# PSoC_Motor_Driver_Design_3.net
KiCad netlist of a schematic drawn in EAGLE
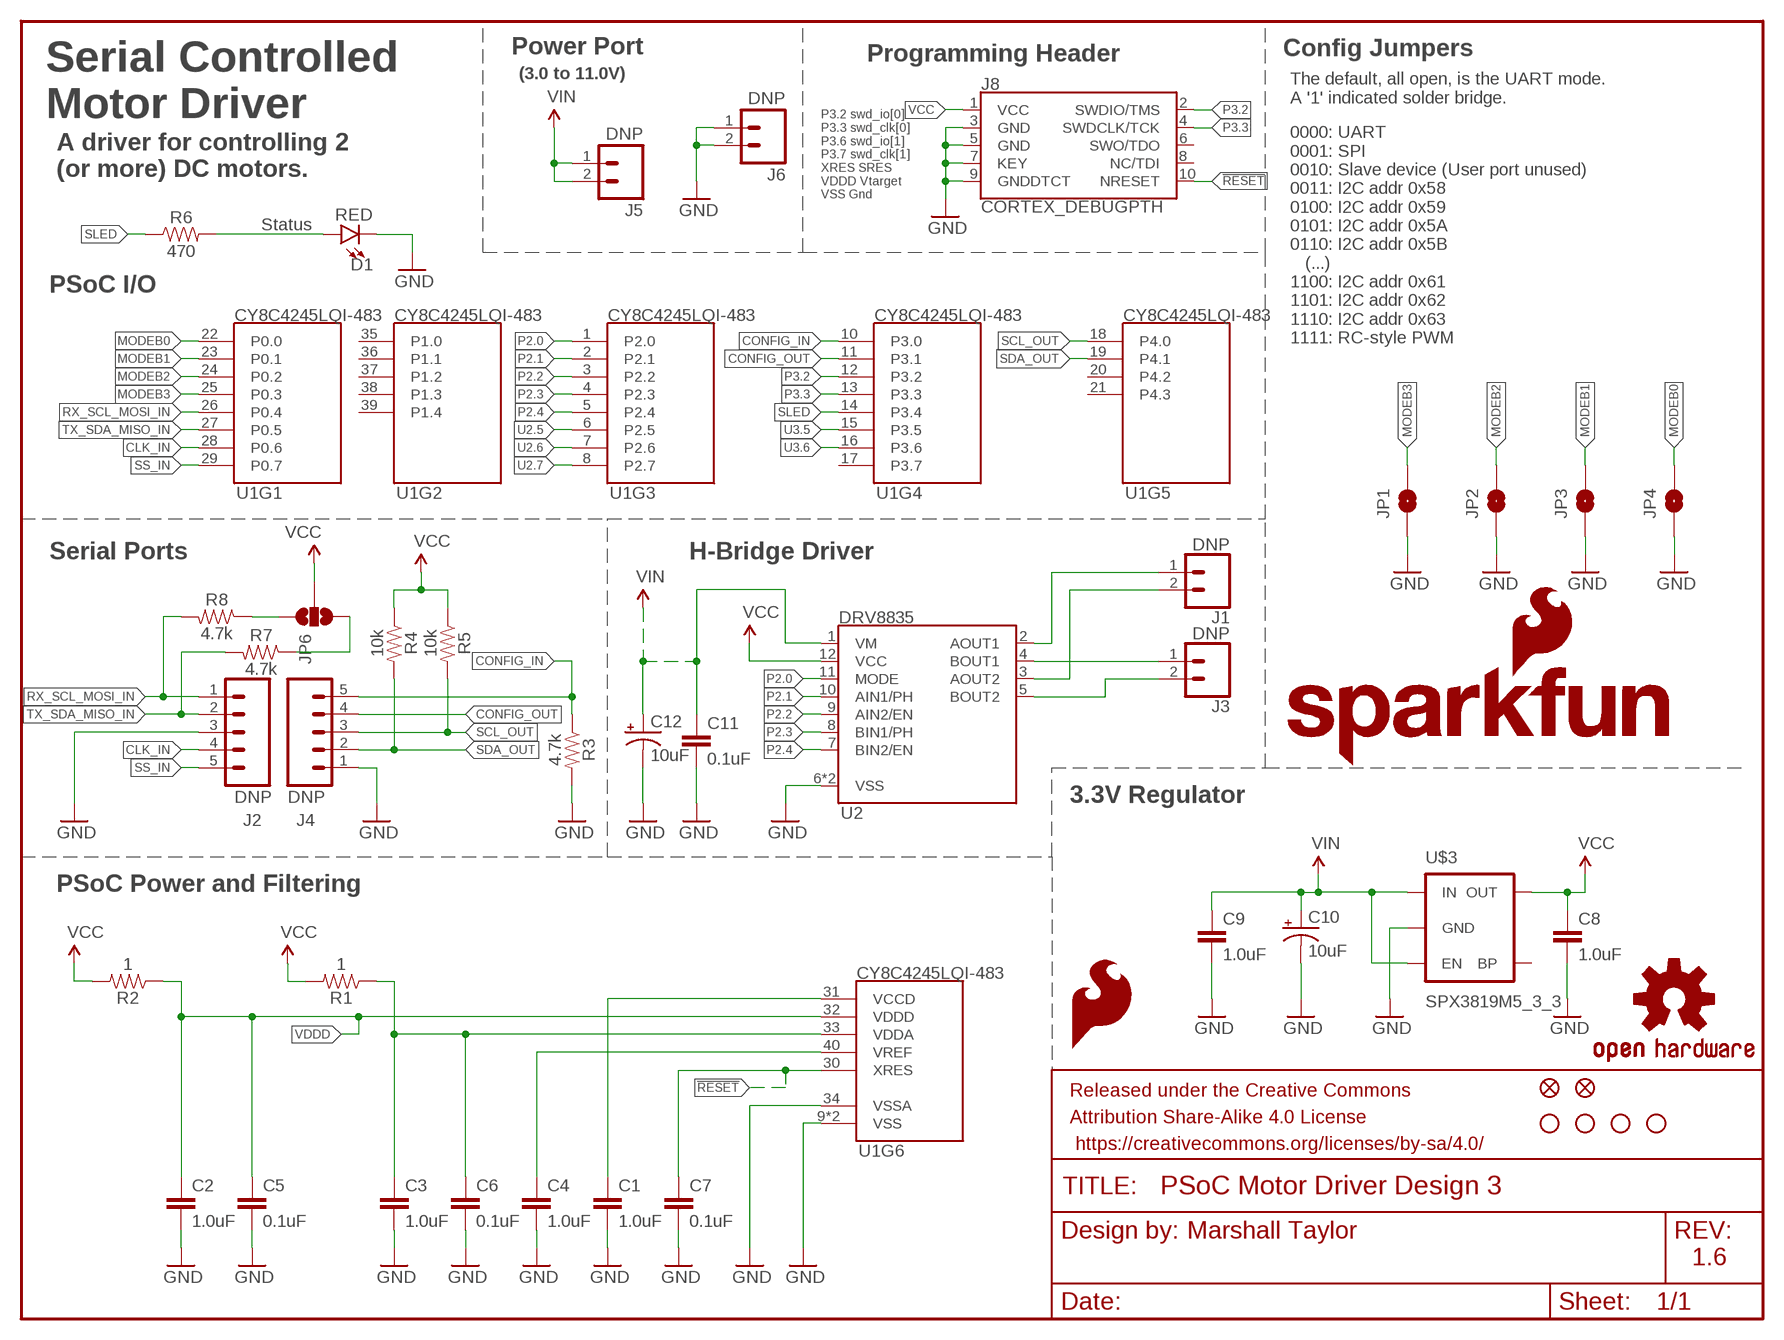
[diagram p0: schematic, sheet 1]

(export (version "E")
  (design (tool "Eeschema 10.0.6"))
  (components
    (comp (ref "C1")
      (value "1.0uF")
      (footprint "eagle-import:0402")
      (libsource (lib "eagle-import") (part "1.0UF-0402-16V-10%"))
    )
    (comp (ref "C2")
      (value "1.0uF")
      (footprint "eagle-import:0402")
      (libsource (lib "eagle-import") (part "1.0UF-0402-16V-10%"))
    )
    (comp (ref "C3")
      (value "1.0uF")
      (footprint "eagle-import:0402")
      (libsource (lib "eagle-import") (part "1.0UF-0402-16V-10%"))
    )
    (comp (ref "C4")
      (value "1.0uF")
      (footprint "eagle-import:0402")
      (libsource (lib "eagle-import") (part "1.0UF-0402-16V-10%"))
    )
    (comp (ref "C5")
      (value "0.1uF")
      (footprint "eagle-import:0402")
      (libsource (lib "eagle-import") (part "0.1UF-0402-16V-10%"))
    )
    (comp (ref "C6")
      (value "0.1uF")
      (footprint "eagle-import:0402")
      (libsource (lib "eagle-import") (part "0.1UF-0402-16V-10%"))
    )
    (comp (ref "C7")
      (value "0.1uF")
      (footprint "eagle-import:0402")
      (libsource (lib "eagle-import") (part "0.1UF-0402-16V-10%"))
    )
    (comp (ref "C8")
      (value "1.0uF")
      (footprint "eagle-import:0402")
      (libsource (lib "eagle-import") (part "1.0UF-0402-16V-10%"))
    )
    (comp (ref "C9")
      (value "1.0uF")
      (footprint "eagle-import:0402")
      (libsource (lib "eagle-import") (part "1.0UF-0402-16V-10%"))
    )
    (comp (ref "C10")
      (value "10uF")
      (footprint "eagle-import:EIA3216")
      (libsource (lib "eagle-import") (part "10UF-POLAR-EIA3216-16V-10%(TANT)"))
    )
    (comp (ref "C11")
      (value "0.1uF")
      (footprint "eagle-import:0402")
      (libsource (lib "eagle-import") (part "0.1UF-0402-16V-10%"))
    )
    (comp (ref "C12")
      (value "10uF")
      (footprint "eagle-import:EIA3216")
      (libsource (lib "eagle-import") (part "10UF-POLAR-EIA3216-16V-10%(TANT)"))
    )
    (comp (ref "D1")
      (value "RED")
      (footprint "eagle-import:LED-0603")
      (libsource (lib "eagle-import") (part "LED-RED0603"))
    )
    (comp (ref "FD1")
      (value "FIDUCIALUFIDUCIAL")
      (footprint "eagle-import:MICRO-FIDUCIAL")
      (libsource (lib "eagle-import") (part "FIDUCIALUFIDUCIAL"))
    )
    (comp (ref "FD2")
      (value "FIDUCIALUFIDUCIAL")
      (footprint "eagle-import:MICRO-FIDUCIAL")
      (libsource (lib "eagle-import") (part "FIDUCIALUFIDUCIAL"))
    )
    (comp (ref "FRAME1")
      (value "FRAME-LETTER")
      (footprint "eagle-import:CREATIVE_COMMONS")
      (libsource (lib "eagle-import") (part "FRAME-LETTER"))
    )
    (comp (ref "H1")
      (value "STAND-OFF")
      (footprint "eagle-import:STAND-OFF")
      (libsource (lib "eagle-import") (part "STAND-OFF"))
    )
    (comp (ref "H2")
      (value "STAND-OFF")
      (footprint "eagle-import:STAND-OFF")
      (libsource (lib "eagle-import") (part "STAND-OFF"))
    )
    (comp (ref "H3")
      (value "STAND-OFF")
      (footprint "eagle-import:STAND-OFF")
      (libsource (lib "eagle-import") (part "STAND-OFF"))
    )
    (comp (ref "H4")
      (value "STAND-OFF")
      (footprint "eagle-import:STAND-OFF")
      (libsource (lib "eagle-import") (part "STAND-OFF"))
    )
    (comp (ref "J1")
      (value "DNP")
      (footprint "eagle-import:1X02_NO_SILK")
      (libsource (lib "eagle-import") (part "CONN_021X02_NO_SILK"))
    )
    (comp (ref "J2")
      (value "DNP")
      (footprint "eagle-import:1X05")
      (libsource (lib "eagle-import") (part "M05PTH"))
    )
    (comp (ref "J3")
      (value "DNP")
      (footprint "eagle-import:1X02_NO_SILK")
      (libsource (lib "eagle-import") (part "CONN_021X02_NO_SILK"))
    )
    (comp (ref "J4")
      (value "DNP")
      (footprint "eagle-import:1X05")
      (libsource (lib "eagle-import") (part "M05PTH"))
    )
    (comp (ref "J5")
      (value "DNP")
      (footprint "eagle-import:1X02@1")
      (libsource (lib "eagle-import") (part "M02PTH"))
    )
    (comp (ref "J6")
      (value "DNP")
      (footprint "eagle-import:1X02@1")
      (libsource (lib "eagle-import") (part "M02PTH"))
    )
    (comp (ref "J8")
      (value "CORTEX_DEBUGPTH")
      (footprint "eagle-import:2X5-PTH-1.27MM")
      (libsource (lib "eagle-import") (part "CORTEX_DEBUGPTH"))
    )
    (comp (ref "JP1")
      (value "JUMPER-PAD-2")
      (footprint "eagle-import:PAD-JUMPER-2-NO_YES_SILK")
      (libsource (lib "eagle-import") (part "JUMPER-PAD-2-NOYES_SILK"))
    )
    (comp (ref "JP2")
      (value "JUMPER-PAD-2")
      (footprint "eagle-import:PAD-JUMPER-2-NO_YES_SILK")
      (libsource (lib "eagle-import") (part "JUMPER-PAD-2-NOYES_SILK"))
    )
    (comp (ref "JP3")
      (value "JUMPER-PAD-2")
      (footprint "eagle-import:PAD-JUMPER-2-NO_YES_SILK")
      (libsource (lib "eagle-import") (part "JUMPER-PAD-2-NOYES_SILK"))
    )
    (comp (ref "JP4")
      (value "JUMPER-PAD-2")
      (footprint "eagle-import:PAD-JUMPER-2-NO_YES_SILK")
      (libsource (lib "eagle-import") (part "JUMPER-PAD-2-NOYES_SILK"))
    )
    (comp (ref "JP6")
      (value "JUMPER-PAD-3-NOYES_SILK")
      (footprint "eagle-import:PAD-JUMPER-3-NO_YES_SILK")
      (libsource (lib "eagle-import") (part "JUMPER-PAD-3-NOYES_SILK"))
    )
    (comp (ref "LOGO1")
      (value "SFE_LOGO_FLAME.1_INCH")
      (footprint "eagle-import:SFE_LOGO_FLAME_.1")
      (libsource (lib "eagle-import") (part "SFE_LOGO_FLAME.1_INCH"))
    )
    (comp (ref "LOGO2")
      (value "OSHW-LOGOMINI")
      (footprint "eagle-import:OSHW-LOGO-MINI")
      (libsource (lib "eagle-import") (part "OSHW-LOGOMINI"))
    )
    (comp (ref "LOGO3")
      (value "SFE_LOGO_NAME_FLAME.1_INCH")
      (footprint "eagle-import:SFE_LOGO_NAME_FLAME_.1")
      (libsource (lib "eagle-import") (part "SFE_LOGO_NAME_FLAME.1_INCH"))
    )
    (comp (ref "R1")
      (value "1")
      (footprint "eagle-import:0603")
      (libsource (lib "eagle-import") (part "1OHM-0603-1/10W-1%"))
    )
    (comp (ref "R2")
      (value "1")
      (footprint "eagle-import:0603")
      (libsource (lib "eagle-import") (part "1OHM-0603-1/10W-1%"))
    )
    (comp (ref "R3")
      (value "4.7k")
      (footprint "eagle-import:0603")
      (libsource (lib "eagle-import") (part "4.7KOHM-0603-1/10W-1%"))
    )
    (comp (ref "R4")
      (value "10k")
      (footprint "eagle-import:0603")
      (libsource (lib "eagle-import") (part "10KOHM-0603-1/10W-1%"))
    )
    (comp (ref "R5")
      (value "10k")
      (footprint "eagle-import:0603")
      (libsource (lib "eagle-import") (part "10KOHM-0603-1/10W-1%"))
    )
    (comp (ref "R6")
      (value "470")
      (footprint "eagle-import:0603")
      (libsource (lib "eagle-import") (part "470OHM-0603-1/10W-1%"))
    )
    (comp (ref "R7")
      (value "4.7k")
      (footprint "eagle-import:0603")
      (libsource (lib "eagle-import") (part "4.7KOHM-0603-1/10W-1%"))
    )
    (comp (ref "R8")
      (value "4.7k")
      (footprint "eagle-import:0603")
      (libsource (lib "eagle-import") (part "4.7KOHM-0603-1/10W-1%"))
    )
    (comp (ref "U$3")
      (value "SPX3819M5_3_3")
      (footprint "eagle-import:SOT-23-5-VREG")
      (libsource (lib "eagle-import") (part "SPX3819"))
    )
    (comp (ref "U1")
      (value "CY8C4245LQI-483")
      (footprint "eagle-import:QFN-40")
      (libsource (lib "eagle-import") (part "CY8C4245LQI"))
    )
    (comp (ref "U2")
      (value "DRV8835")
      (footprint "eagle-import:WSON-12")
      (fields (field (name "PROD_ID") "IC-13342"))
      (libsource (lib "eagle-import") (part "DRV883X"))
    )
  )
  (nets
    (net (code "1") (name "/~{RESET}") (class "Default")
      (node (ref "C7") (pin "1") (pinfunction "1_1") (pintype "passive"))
      (node (ref "J8") (pin "10") (pinfunction "NRESET_10") (pintype "bidirectional"))
      (node (ref "U1") (pin "30") (pinfunction "XRES_30") (pintype "bidirectional"))
    )
    (net (code "2") (name "CLK_IN") (class "Default")
      (node (ref "J2") (pin "4") (pinfunction "4_4") (pintype "passive"))
      (node (ref "U1") (pin "28") (pinfunction "P0.6_28") (pintype "bidirectional"))
    )
    (net (code "3") (name "CONFIG_IN") (class "Default")
      (node (ref "J4") (pin "5") (pinfunction "5_5") (pintype "passive"))
      (node (ref "R3") (pin "1") (pinfunction "1_1") (pintype "passive"))
      (node (ref "U1") (pin "10") (pinfunction "P3.0_10") (pintype "bidirectional"))
    )
    (net (code "4") (name "CONFIG_OUT") (class "Default")
      (node (ref "J4") (pin "4") (pinfunction "4_4") (pintype "passive"))
      (node (ref "U1") (pin "11") (pinfunction "P3.1_11") (pintype "bidirectional"))
    )
    (net (code "5") (name "GND") (class "Default")
      (node (ref "C1") (pin "2") (pinfunction "2_2") (pintype "passive"))
      (node (ref "C10") (pin "-") (pinfunction "-_-") (pintype "passive"))
      (node (ref "C11") (pin "2") (pinfunction "2_2") (pintype "passive"))
      (node (ref "C12") (pin "-") (pinfunction "-_-") (pintype "passive"))
      (node (ref "C2") (pin "2") (pinfunction "2_2") (pintype "passive"))
      (node (ref "C3") (pin "2") (pinfunction "2_2") (pintype "passive"))
      (node (ref "C4") (pin "2") (pinfunction "2_2") (pintype "passive"))
      (node (ref "C5") (pin "2") (pinfunction "2_2") (pintype "passive"))
      (node (ref "C6") (pin "2") (pinfunction "2_2") (pintype "passive"))
      (node (ref "C7") (pin "2") (pinfunction "2_2") (pintype "passive"))
      (node (ref "C8") (pin "2") (pinfunction "2_2") (pintype "passive"))
      (node (ref "C9") (pin "2") (pinfunction "2_2") (pintype "passive"))
      (node (ref "D1") (pin "C") (pinfunction "C_C") (pintype "passive"))
      (node (ref "J2") (pin "3") (pinfunction "3_3") (pintype "passive"))
      (node (ref "J4") (pin "1") (pinfunction "1_1") (pintype "passive"))
      (node (ref "J6") (pin "1") (pinfunction "1_1") (pintype "passive"))
      (node (ref "J6") (pin "2") (pinfunction "2_2") (pintype "passive"))
      (node (ref "J8") (pin "3") (pinfunction "GND_3") (pintype "bidirectional"))
      (node (ref "J8") (pin "5") (pinfunction "GND_5") (pintype "bidirectional"))
      (node (ref "J8") (pin "7") (pinfunction "KEY_7") (pintype "bidirectional"))
      (node (ref "J8") (pin "9") (pinfunction "GNDDTCT_9") (pintype "bidirectional"))
      (node (ref "JP1") (pin "1") (pinfunction "1_1") (pintype "passive"))
      (node (ref "JP2") (pin "1") (pinfunction "1_1") (pintype "passive"))
      (node (ref "JP3") (pin "1") (pinfunction "1_1") (pintype "passive"))
      (node (ref "JP4") (pin "1") (pinfunction "1_1") (pintype "passive"))
      (node (ref "R3") (pin "2") (pinfunction "2_2") (pintype "passive"))
      (node (ref "U$3") (pin "2") (pinfunction "GND_2") (pintype "input"))
      (node (ref "U1") (pin "34") (pinfunction "VSSA_34") (pintype "bidirectional"))
      (node (ref "U1") (pin "9") (pinfunction "VSS_9") (pintype "bidirectional"))
      (node (ref "U1") (pin "EP") (pinfunction "VSS_EP") (pintype "bidirectional"))
      (node (ref "U2") (pin "6") (pinfunction "VSS_6") (pintype "bidirectional"))
      (node (ref "U2") (pin "PAD") (pinfunction "VSS_PAD") (pintype "bidirectional"))
    )
    (net (code "6") (name "MODEB0") (class "Default")
      (node (ref "JP4") (pin "2") (pinfunction "2_2") (pintype "passive"))
      (node (ref "U1") (pin "22") (pinfunction "P0.0_22") (pintype "bidirectional"))
    )
    (net (code "7") (name "MODEB1") (class "Default")
      (node (ref "JP3") (pin "2") (pinfunction "2_2") (pintype "passive"))
      (node (ref "U1") (pin "23") (pinfunction "P0.1_23") (pintype "bidirectional"))
    )
    (net (code "8") (name "MODEB2") (class "Default")
      (node (ref "JP2") (pin "2") (pinfunction "2_2") (pintype "passive"))
      (node (ref "U1") (pin "24") (pinfunction "P0.2_24") (pintype "bidirectional"))
    )
    (net (code "9") (name "MODEB3") (class "Default")
      (node (ref "JP1") (pin "2") (pinfunction "2_2") (pintype "passive"))
      (node (ref "U1") (pin "25") (pinfunction "P0.3_25") (pintype "bidirectional"))
    )
    (net (code "10") (name "Net-(D1-PadA)") (class "Default")
      (node (ref "D1") (pin "A") (pinfunction "A_A") (pintype "passive"))
      (node (ref "R6") (pin "2") (pinfunction "2_2") (pintype "passive"))
    )
    (net (code "11") (name "Net-(JP6-Pad1)") (class "Default")
      (node (ref "JP6") (pin "1") (pinfunction "1_1") (pintype "passive"))
      (node (ref "R8") (pin "1") (pinfunction "1_1") (pintype "passive"))
    )
    (net (code "12") (name "Net-(JP6-Pad3)") (class "Default")
      (node (ref "JP6") (pin "3") (pinfunction "3_3") (pintype "passive"))
      (node (ref "R7") (pin "1") (pinfunction "1_1") (pintype "passive"))
    )
    (net (code "13") (name "Net-(U1F-VCCD)") (class "Default")
      (node (ref "C1") (pin "1") (pinfunction "1_1") (pintype "passive"))
      (node (ref "U1") (pin "31") (pinfunction "VCCD_31") (pintype "bidirectional"))
    )
    (net (code "14") (name "Net-(U1F-VDDA)") (class "Default")
      (node (ref "C3") (pin "1") (pinfunction "1_1") (pintype "passive"))
      (node (ref "C6") (pin "1") (pinfunction "1_1") (pintype "passive"))
      (node (ref "R1") (pin "1") (pinfunction "1_1") (pintype "passive"))
      (node (ref "U1") (pin "33") (pinfunction "VDDA_33") (pintype "bidirectional"))
    )
    (net (code "15") (name "Net-(U1F-VREF)") (class "Default")
      (node (ref "C4") (pin "1") (pinfunction "1_1") (pintype "passive"))
      (node (ref "U1") (pin "40") (pinfunction "VREF_40") (pintype "bidirectional"))
    )
    (net (code "16") (name "Net-(U2-AOUT1)") (class "Default")
      (node (ref "J1") (pin "1") (pinfunction "1_1") (pintype "passive"))
      (node (ref "U2") (pin "2") (pinfunction "AOUT1_2") (pintype "bidirectional"))
    )
    (net (code "17") (name "Net-(U2-AOUT2)") (class "Default")
      (node (ref "J1") (pin "2") (pinfunction "2_2") (pintype "passive"))
      (node (ref "U2") (pin "3") (pinfunction "AOUT2_3") (pintype "bidirectional"))
    )
    (net (code "18") (name "Net-(U2-BOUT1)") (class "Default")
      (node (ref "J3") (pin "1") (pinfunction "1_1") (pintype "passive"))
      (node (ref "U2") (pin "4") (pinfunction "BOUT1_4") (pintype "bidirectional"))
    )
    (net (code "19") (name "Net-(U2-BOUT2)") (class "Default")
      (node (ref "J3") (pin "2") (pinfunction "2_2") (pintype "passive"))
      (node (ref "U2") (pin "5") (pinfunction "BOUT2_5") (pintype "bidirectional"))
    )
    (net (code "20") (name "P2.0") (class "Default")
      (node (ref "U1") (pin "1") (pinfunction "P2.0_1") (pintype "bidirectional"))
      (node (ref "U2") (pin "11") (pinfunction "MODE_11") (pintype "bidirectional"))
    )
    (net (code "21") (name "P2.1") (class "Default")
      (node (ref "U1") (pin "2") (pinfunction "P2.1_2") (pintype "bidirectional"))
      (node (ref "U2") (pin "10") (pinfunction "AIN1/PH_10") (pintype "bidirectional"))
    )
    (net (code "22") (name "P2.2") (class "Default")
      (node (ref "U1") (pin "3") (pinfunction "P2.2_3") (pintype "bidirectional"))
      (node (ref "U2") (pin "9") (pinfunction "AIN2/EN_9") (pintype "bidirectional"))
    )
    (net (code "23") (name "P2.3") (class "Default")
      (node (ref "U1") (pin "4") (pinfunction "P2.3_4") (pintype "bidirectional"))
      (node (ref "U2") (pin "8") (pinfunction "BIN1/PH_8") (pintype "bidirectional"))
    )
    (net (code "24") (name "P2.4") (class "Default")
      (node (ref "U1") (pin "5") (pinfunction "P2.4_5") (pintype "bidirectional"))
      (node (ref "U2") (pin "7") (pinfunction "BIN2/EN_7") (pintype "bidirectional"))
    )
    (net (code "25") (name "P3.2") (class "Default")
      (node (ref "J8") (pin "2") (pinfunction "SWDIO/TMS_2") (pintype "bidirectional"))
      (node (ref "U1") (pin "12") (pinfunction "P3.2_12") (pintype "bidirectional"))
    )
    (net (code "26") (name "P3.3") (class "Default")
      (node (ref "J8") (pin "4") (pinfunction "SWDCLK/TCK_4") (pintype "bidirectional"))
      (node (ref "U1") (pin "13") (pinfunction "P3.3_13") (pintype "bidirectional"))
    )
    (net (code "27") (name "RX_SCL_MOSI_IN") (class "Default")
      (node (ref "J2") (pin "1") (pinfunction "1_1") (pintype "passive"))
      (node (ref "R8") (pin "2") (pinfunction "2_2") (pintype "passive"))
      (node (ref "U1") (pin "26") (pinfunction "P0.4_26") (pintype "bidirectional"))
    )
    (net (code "28") (name "SCL_OUT") (class "Default")
      (node (ref "J4") (pin "3") (pinfunction "3_3") (pintype "passive"))
      (node (ref "R5") (pin "2") (pinfunction "2_2") (pintype "passive"))
      (node (ref "U1") (pin "18") (pinfunction "P4.0_18") (pintype "bidirectional"))
    )
    (net (code "29") (name "SDA_OUT") (class "Default")
      (node (ref "J4") (pin "2") (pinfunction "2_2") (pintype "passive"))
      (node (ref "R4") (pin "2") (pinfunction "2_2") (pintype "passive"))
      (node (ref "U1") (pin "19") (pinfunction "P4.1_19") (pintype "bidirectional"))
    )
    (net (code "30") (name "SLED") (class "Default")
      (node (ref "R6") (pin "1") (pinfunction "1_1") (pintype "passive"))
      (node (ref "U1") (pin "14") (pinfunction "P3.4_14") (pintype "bidirectional"))
    )
    (net (code "31") (name "SS_IN") (class "Default")
      (node (ref "J2") (pin "5") (pinfunction "5_5") (pintype "passive"))
      (node (ref "U1") (pin "29") (pinfunction "P0.7_29") (pintype "bidirectional"))
    )
    (net (code "32") (name "TX_SDA_MISO_IN") (class "Default")
      (node (ref "J2") (pin "2") (pinfunction "2_2") (pintype "passive"))
      (node (ref "R7") (pin "2") (pinfunction "2_2") (pintype "passive"))
      (node (ref "U1") (pin "27") (pinfunction "P0.5_27") (pintype "bidirectional"))
    )
    (net (code "33") (name "U2.5") (class "Default")
      (node (ref "U1") (pin "6") (pinfunction "P2.5_6") (pintype "bidirectional"))
    )
    (net (code "34") (name "U2.6") (class "Default")
      (node (ref "U1") (pin "7") (pinfunction "P2.6_7") (pintype "bidirectional"))
    )
    (net (code "35") (name "U2.7") (class "Default")
      (node (ref "U1") (pin "8") (pinfunction "P2.7_8") (pintype "bidirectional"))
    )
    (net (code "36") (name "U3.5") (class "Default")
      (node (ref "U1") (pin "15") (pinfunction "P3.5_15") (pintype "bidirectional"))
    )
    (net (code "37") (name "U3.6") (class "Default")
      (node (ref "U1") (pin "16") (pinfunction "P3.6_16") (pintype "bidirectional"))
    )
    (net (code "38") (name "VCC") (class "Default")
      (node (ref "C8") (pin "1") (pinfunction "1_1") (pintype "passive"))
      (node (ref "J8") (pin "1") (pinfunction "VCC_1") (pintype "bidirectional"))
      (node (ref "JP6") (pin "2") (pinfunction "2_2") (pintype "passive"))
      (node (ref "R1") (pin "2") (pinfunction "2_2") (pintype "passive"))
      (node (ref "R2") (pin "2") (pinfunction "2_2") (pintype "passive"))
      (node (ref "R4") (pin "1") (pinfunction "1_1") (pintype "passive"))
      (node (ref "R5") (pin "1") (pinfunction "1_1") (pintype "passive"))
      (node (ref "U$3") (pin "5") (pinfunction "OUT_5") (pintype "passive"))
      (node (ref "U2") (pin "12") (pinfunction "VCC_12") (pintype "bidirectional"))
    )
    (net (code "39") (name "VDDD") (class "Default")
      (node (ref "C2") (pin "1") (pinfunction "1_1") (pintype "passive"))
      (node (ref "C5") (pin "1") (pinfunction "1_1") (pintype "passive"))
      (node (ref "R2") (pin "1") (pinfunction "1_1") (pintype "passive"))
      (node (ref "U1") (pin "32") (pinfunction "VDDD_32") (pintype "bidirectional"))
    )
    (net (code "40") (name "VIN") (class "Default")
      (node (ref "C10") (pin "+") (pinfunction "+_+") (pintype "passive"))
      (node (ref "C11") (pin "1") (pinfunction "1_1") (pintype "passive"))
      (node (ref "C12") (pin "+") (pinfunction "+_+") (pintype "passive"))
      (node (ref "C9") (pin "1") (pinfunction "1_1") (pintype "passive"))
      (node (ref "J5") (pin "1") (pinfunction "1_1") (pintype "passive"))
      (node (ref "J5") (pin "2") (pinfunction "2_2") (pintype "passive"))
      (node (ref "U$3") (pin "1") (pinfunction "IN_1") (pintype "input"))
      (node (ref "U$3") (pin "3") (pinfunction "EN_3") (pintype "input"))
      (node (ref "U2") (pin "1") (pinfunction "VM_1") (pintype "bidirectional"))
    )
    (net (code "41") (name "unconnected-(J8-NC{slash}TDI-Pad8)") (class "Default")
      (node (ref "J8") (pin "8") (pinfunction "NC/TDI_8") (pintype "bidirectional"))
    )
    (net (code "42") (name "unconnected-(J8-SWO{slash}TDO-Pad6)") (class "Default")
      (node (ref "J8") (pin "6") (pinfunction "SWO/TDO_6") (pintype "bidirectional"))
    )
    (net (code "43") (name "unconnected-(U$3-BP-Pad4)") (class "Default")
      (node (ref "U$3") (pin "4") (pinfunction "BP_4") (pintype "input"))
    )
    (net (code "44") (name "unconnected-(U1B-P1.0-Pad35)") (class "Default")
      (node (ref "U1") (pin "35") (pinfunction "P1.0_35") (pintype "bidirectional"))
    )
    (net (code "45") (name "unconnected-(U1B-P1.1-Pad36)") (class "Default")
      (node (ref "U1") (pin "36") (pinfunction "P1.1_36") (pintype "bidirectional"))
    )
    (net (code "46") (name "unconnected-(U1B-P1.2-Pad37)") (class "Default")
      (node (ref "U1") (pin "37") (pinfunction "P1.2_37") (pintype "bidirectional"))
    )
    (net (code "47") (name "unconnected-(U1B-P1.3-Pad38)") (class "Default")
      (node (ref "U1") (pin "38") (pinfunction "P1.3_38") (pintype "bidirectional"))
    )
    (net (code "48") (name "unconnected-(U1B-P1.4-Pad39)") (class "Default")
      (node (ref "U1") (pin "39") (pinfunction "P1.4_39") (pintype "bidirectional"))
    )
    (net (code "49") (name "unconnected-(U1D-P3.7-Pad17)") (class "Default")
      (node (ref "U1") (pin "17") (pinfunction "P3.7_17") (pintype "bidirectional"))
    )
    (net (code "50") (name "unconnected-(U1E-P4.2-Pad20)") (class "Default")
      (node (ref "U1") (pin "20") (pinfunction "P4.2_20") (pintype "bidirectional"))
    )
    (net (code "51") (name "unconnected-(U1E-P4.3-Pad21)") (class "Default")
      (node (ref "U1") (pin "21") (pinfunction "P4.3_21") (pintype "bidirectional"))
    )
  )
)
